# piezo-driver_v0_1-R002.net
KiCad netlist of a schematic drawn in EAGLE
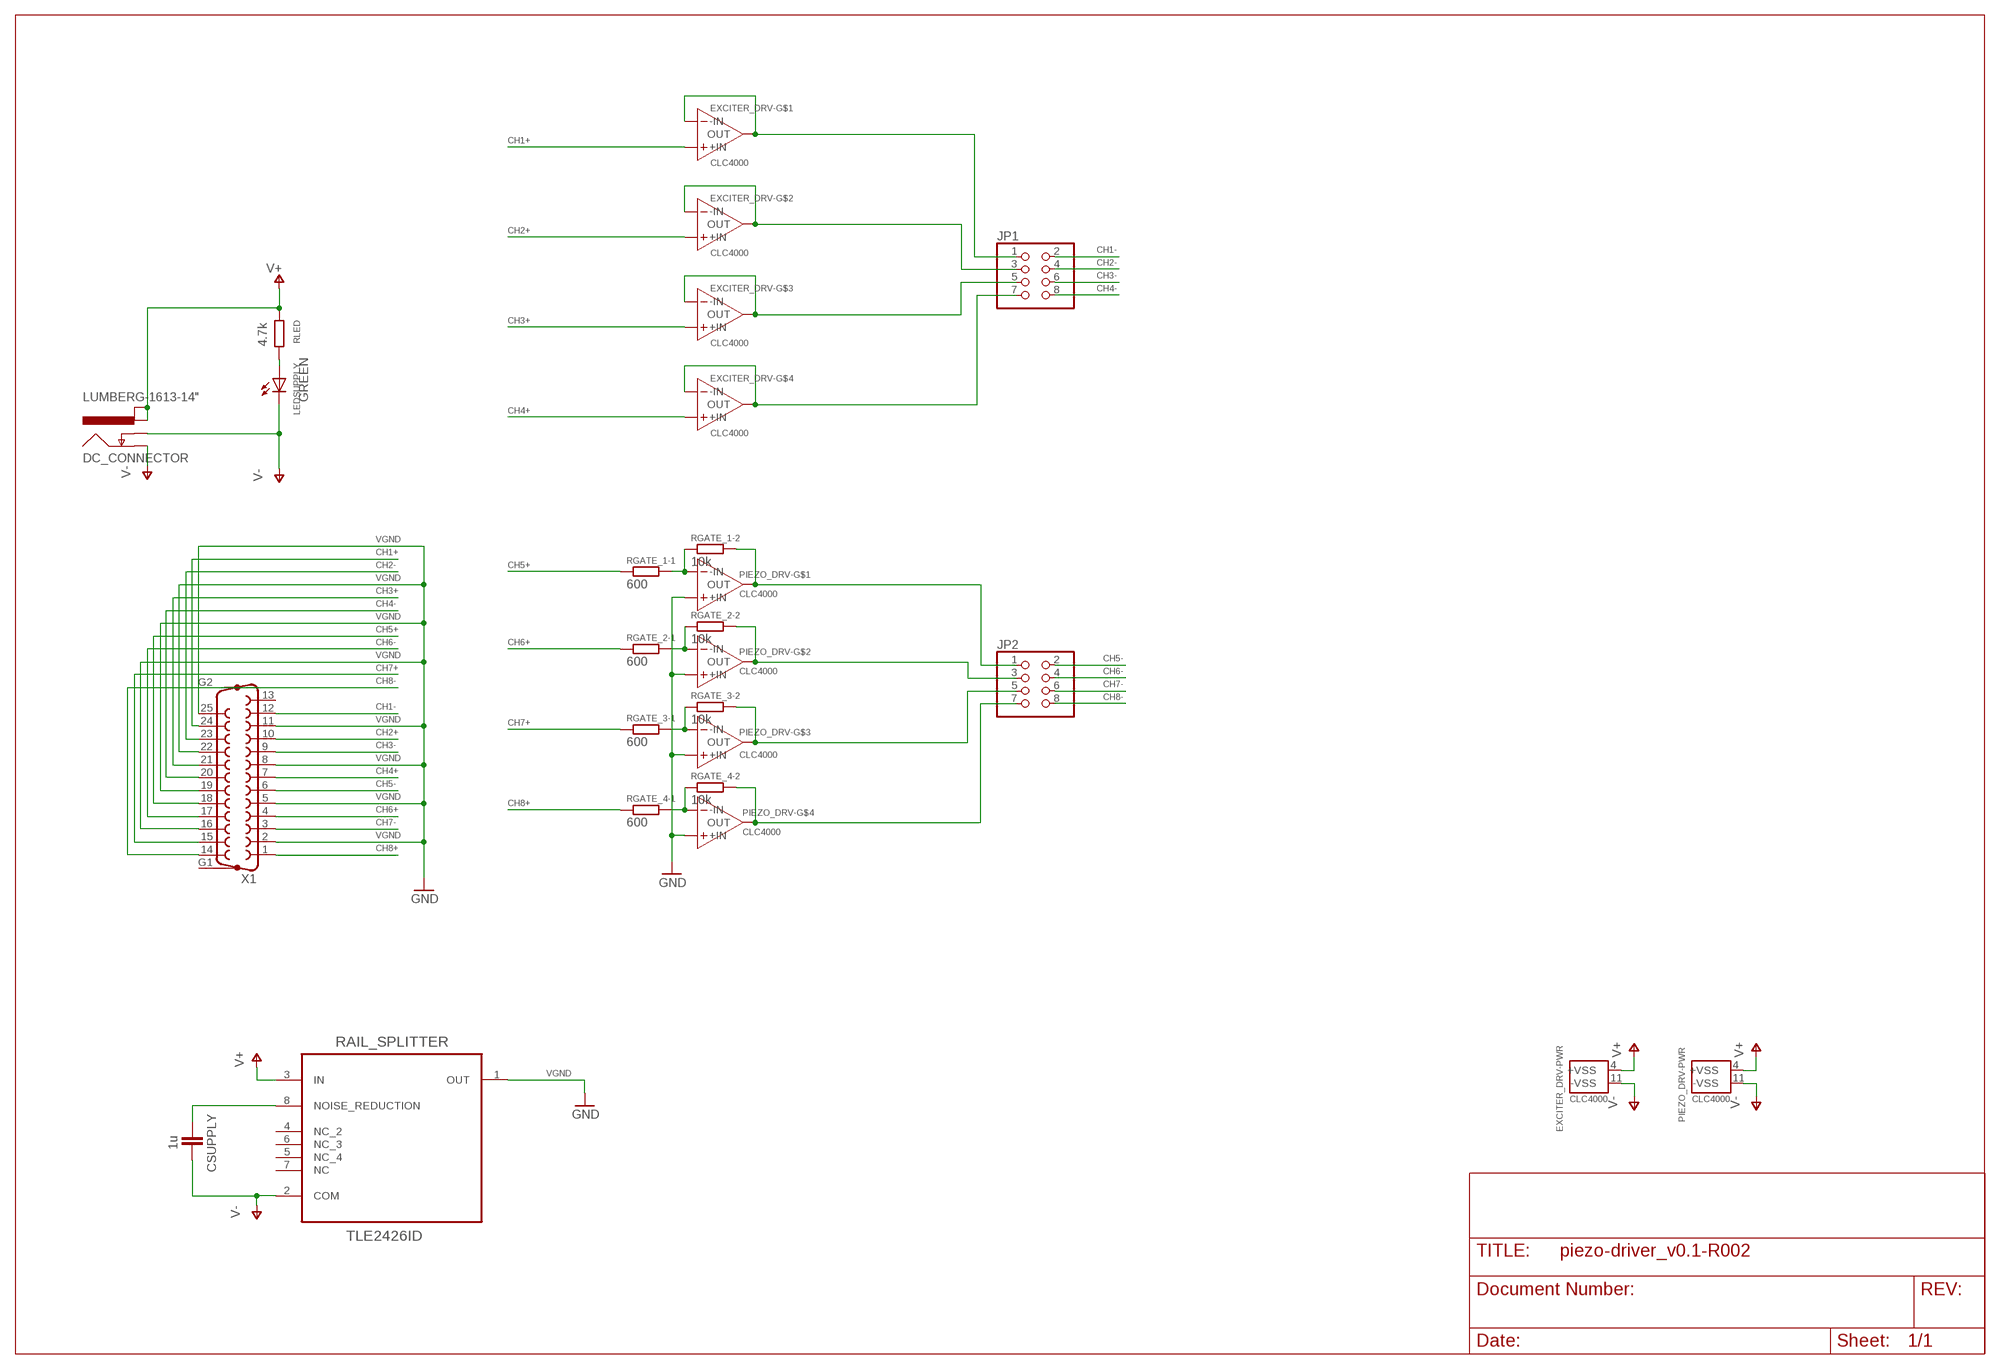
[diagram p0: schematic, sheet 1]

(export (version "E")
  (design (tool "Eeschema 10.0.6"))
  (components
    (comp (ref "CSUPPLY")
      (value "1u")
      (footprint "eagle-import:C0603")
      (libsource (lib "eagle-import") (part "C-EUC0603"))
    )
    (comp (ref "DC_CONNECTOR")
      (value "LUMBERG-1613-14\"")
      (footprint "eagle-import:LUMBERG-1613_14")
      (libsource (lib "eagle-import") (part "LUMBERG-1613-14{dblquote}"))
    )
    (comp (ref "EXCITER_DRV")
      (value "CLC4000")
      (footprint "eagle-import:SOIC-14")
      (libsource (lib "eagle-import") (part "CLC4000"))
    )
    (comp (ref "JP1")
      (value "PINHD-2X4/90")
      (footprint "eagle-import:2X04_90")
      (libsource (lib "eagle-import") (part "PINHD-2X4/90"))
    )
    (comp (ref "JP2")
      (value "PINHD-2X4/90")
      (footprint "eagle-import:2X04_90")
      (libsource (lib "eagle-import") (part "PINHD-2X4/90"))
    )
    (comp (ref "LEDSUPPLY")
      (value "GREEN")
      (footprint "eagle-import:LED3MM")
      (libsource (lib "eagle-import") (part "LED3MM"))
    )
    (comp (ref "PIEZO_DRV")
      (value "CLC4000")
      (footprint "eagle-import:SOIC-14")
      (libsource (lib "eagle-import") (part "CLC4000"))
    )
    (comp (ref "RAIL_SPLITTER")
      (value "TLE2426ID")
      (footprint "eagle-import:SOIC127P600X175-8N")
      (libsource (lib "eagle-import") (part "TLE2426ID"))
    )
    (comp (ref "RGATE_1-1")
      (value "600")
      (footprint "eagle-import:R0805")
      (libsource (lib "eagle-import") (part "R-EU_R0805"))
    )
    (comp (ref "RGATE_1-2")
      (value "10k")
      (footprint "eagle-import:R0805")
      (libsource (lib "eagle-import") (part "R-EU_R0805"))
    )
    (comp (ref "RGATE_2-1")
      (value "600")
      (footprint "eagle-import:R0805")
      (libsource (lib "eagle-import") (part "R-EU_R0805"))
    )
    (comp (ref "RGATE_2-2")
      (value "10k")
      (footprint "eagle-import:R0805")
      (libsource (lib "eagle-import") (part "R-EU_R0805"))
    )
    (comp (ref "RGATE_3-1")
      (value "600")
      (footprint "eagle-import:R0805")
      (libsource (lib "eagle-import") (part "R-EU_R0805"))
    )
    (comp (ref "RGATE_3-2")
      (value "10k")
      (footprint "eagle-import:R0805")
      (libsource (lib "eagle-import") (part "R-EU_R0805"))
    )
    (comp (ref "RGATE_4-1")
      (value "600")
      (footprint "eagle-import:R0805")
      (libsource (lib "eagle-import") (part "R-EU_R0805"))
    )
    (comp (ref "RGATE_4-2")
      (value "10k")
      (footprint "eagle-import:R0805")
      (libsource (lib "eagle-import") (part "R-EU_R0805"))
    )
    (comp (ref "RLED")
      (value "4.7k")
      (footprint "eagle-import:R0805")
      (libsource (lib "eagle-import") (part "R-EU_R0805"))
    )
    (comp (ref "X1")
      (value "F25HP")
      (footprint "eagle-import:F25HP")
      (libsource (lib "eagle-import") (part "F25HP"))
    )
  )
  (nets
    (net (code "1") (name "/CH1+") (class "Default")
      (node (ref "EXCITER_DRV") (pin "3") (pinfunction "+IN_3") (pintype "bidirectional"))
      (node (ref "X1") (pin "24") (pinfunction "24_24") (pintype "passive"))
    )
    (net (code "2") (name "/CH1-") (class "Default")
      (node (ref "JP1") (pin "2") (pinfunction "2_2") (pintype "passive"))
      (node (ref "X1") (pin "12") (pinfunction "12_12") (pintype "passive"))
    )
    (net (code "3") (name "/CH2+") (class "Default")
      (node (ref "EXCITER_DRV") (pin "5") (pinfunction "+IN_5") (pintype "bidirectional"))
      (node (ref "X1") (pin "10") (pinfunction "10_10") (pintype "passive"))
    )
    (net (code "4") (name "/CH2-") (class "Default")
      (node (ref "JP1") (pin "4") (pinfunction "4_4") (pintype "passive"))
      (node (ref "X1") (pin "23") (pinfunction "23_23") (pintype "passive"))
    )
    (net (code "5") (name "/CH3+") (class "Default")
      (node (ref "EXCITER_DRV") (pin "10") (pinfunction "+IN_10") (pintype "bidirectional"))
      (node (ref "X1") (pin "21") (pinfunction "21_21") (pintype "passive"))
    )
    (net (code "6") (name "/CH3-") (class "Default")
      (node (ref "JP1") (pin "6") (pinfunction "6_6") (pintype "passive"))
      (node (ref "X1") (pin "9") (pinfunction "9_9") (pintype "passive"))
    )
    (net (code "7") (name "/CH4+") (class "Default")
      (node (ref "EXCITER_DRV") (pin "12") (pinfunction "+IN_12") (pintype "bidirectional"))
      (node (ref "X1") (pin "7") (pinfunction "7_7") (pintype "passive"))
    )
    (net (code "8") (name "/CH4-") (class "Default")
      (node (ref "JP1") (pin "8") (pinfunction "8_8") (pintype "passive"))
      (node (ref "X1") (pin "20") (pinfunction "20_20") (pintype "passive"))
    )
    (net (code "9") (name "/CH5+") (class "Default")
      (node (ref "RGATE_1-1") (pin "1") (pinfunction "1_1") (pintype "passive"))
      (node (ref "X1") (pin "18") (pinfunction "18_18") (pintype "passive"))
    )
    (net (code "10") (name "/CH5-") (class "Default")
      (node (ref "JP2") (pin "2") (pinfunction "2_2") (pintype "passive"))
      (node (ref "X1") (pin "6") (pinfunction "6_6") (pintype "passive"))
    )
    (net (code "11") (name "/CH6+") (class "Default")
      (node (ref "RGATE_2-1") (pin "1") (pinfunction "1_1") (pintype "passive"))
      (node (ref "X1") (pin "4") (pinfunction "4_4") (pintype "passive"))
    )
    (net (code "12") (name "/CH6-") (class "Default")
      (node (ref "JP2") (pin "4") (pinfunction "4_4") (pintype "passive"))
      (node (ref "X1") (pin "17") (pinfunction "17_17") (pintype "passive"))
    )
    (net (code "13") (name "/CH7+") (class "Default")
      (node (ref "RGATE_3-1") (pin "1") (pinfunction "1_1") (pintype "passive"))
      (node (ref "X1") (pin "15") (pinfunction "15_15") (pintype "passive"))
    )
    (net (code "14") (name "/CH7-") (class "Default")
      (node (ref "JP2") (pin "6") (pinfunction "6_6") (pintype "passive"))
      (node (ref "X1") (pin "3") (pinfunction "3_3") (pintype "passive"))
    )
    (net (code "15") (name "/CH8+") (class "Default")
      (node (ref "RGATE_4-1") (pin "1") (pinfunction "1_1") (pintype "passive"))
      (node (ref "X1") (pin "1") (pinfunction "1_1") (pintype "passive"))
    )
    (net (code "16") (name "/CH8-") (class "Default")
      (node (ref "JP2") (pin "8") (pinfunction "8_8") (pintype "passive"))
      (node (ref "X1") (pin "14") (pinfunction "14_14") (pintype "passive"))
    )
    (net (code "17") (name "GND") (class "Default")
      (node (ref "PIEZO_DRV") (pin "10") (pinfunction "+IN_10") (pintype "bidirectional"))
      (node (ref "PIEZO_DRV") (pin "12") (pinfunction "+IN_12") (pintype "bidirectional"))
      (node (ref "PIEZO_DRV") (pin "3") (pinfunction "+IN_3") (pintype "bidirectional"))
      (node (ref "PIEZO_DRV") (pin "5") (pinfunction "+IN_5") (pintype "bidirectional"))
      (node (ref "RAIL_SPLITTER") (pin "1") (pinfunction "OUT_1") (pintype "output"))
      (node (ref "X1") (pin "11") (pinfunction "11_11") (pintype "passive"))
      (node (ref "X1") (pin "16") (pinfunction "16_16") (pintype "passive"))
      (node (ref "X1") (pin "19") (pinfunction "19_19") (pintype "passive"))
      (node (ref "X1") (pin "2") (pinfunction "2_2") (pintype "passive"))
      (node (ref "X1") (pin "22") (pinfunction "22_22") (pintype "passive"))
      (node (ref "X1") (pin "25") (pinfunction "25_25") (pintype "passive"))
      (node (ref "X1") (pin "5") (pinfunction "5_5") (pintype "passive"))
      (node (ref "X1") (pin "8") (pinfunction "8_8") (pintype "passive"))
    )
    (net (code "18") (name "Net-(EXCITER_DRVA--IN)") (class "Default")
      (node (ref "EXCITER_DRV") (pin "1") (pinfunction "OUT_1") (pintype "bidirectional"))
      (node (ref "EXCITER_DRV") (pin "2") (pinfunction "-IN_2") (pintype "bidirectional"))
      (node (ref "JP1") (pin "1") (pinfunction "1_1") (pintype "passive"))
    )
    (net (code "19") (name "Net-(EXCITER_DRVB--IN)") (class "Default")
      (node (ref "EXCITER_DRV") (pin "6") (pinfunction "-IN_6") (pintype "bidirectional"))
      (node (ref "EXCITER_DRV") (pin "7") (pinfunction "OUT_7") (pintype "bidirectional"))
      (node (ref "JP1") (pin "3") (pinfunction "3_3") (pintype "passive"))
    )
    (net (code "20") (name "Net-(EXCITER_DRVC--IN)") (class "Default")
      (node (ref "EXCITER_DRV") (pin "8") (pinfunction "OUT_8") (pintype "bidirectional"))
      (node (ref "EXCITER_DRV") (pin "9") (pinfunction "-IN_9") (pintype "bidirectional"))
      (node (ref "JP1") (pin "5") (pinfunction "5_5") (pintype "passive"))
    )
    (net (code "21") (name "Net-(EXCITER_DRVD--IN)") (class "Default")
      (node (ref "EXCITER_DRV") (pin "13") (pinfunction "-IN_13") (pintype "bidirectional"))
      (node (ref "EXCITER_DRV") (pin "14") (pinfunction "OUT_14") (pintype "bidirectional"))
      (node (ref "JP1") (pin "7") (pinfunction "7_7") (pintype "passive"))
    )
    (net (code "22") (name "Net-(LEDSUPPLY-PadA)") (class "Default")
      (node (ref "LEDSUPPLY") (pin "A") (pinfunction "A_A") (pintype "passive"))
      (node (ref "RLED") (pin "1") (pinfunction "1_1") (pintype "passive"))
    )
    (net (code "23") (name "Net-(PIEZO_DRVA--IN)") (class "Default")
      (node (ref "PIEZO_DRV") (pin "2") (pinfunction "-IN_2") (pintype "bidirectional"))
      (node (ref "RGATE_1-1") (pin "2") (pinfunction "2_2") (pintype "passive"))
      (node (ref "RGATE_1-2") (pin "1") (pinfunction "1_1") (pintype "passive"))
    )
    (net (code "24") (name "Net-(PIEZO_DRVA-OUT)") (class "Default")
      (node (ref "JP2") (pin "1") (pinfunction "1_1") (pintype "passive"))
      (node (ref "PIEZO_DRV") (pin "1") (pinfunction "OUT_1") (pintype "bidirectional"))
      (node (ref "RGATE_1-2") (pin "2") (pinfunction "2_2") (pintype "passive"))
    )
    (net (code "25") (name "Net-(PIEZO_DRVB--IN)") (class "Default")
      (node (ref "PIEZO_DRV") (pin "6") (pinfunction "-IN_6") (pintype "bidirectional"))
      (node (ref "RGATE_2-1") (pin "2") (pinfunction "2_2") (pintype "passive"))
      (node (ref "RGATE_2-2") (pin "1") (pinfunction "1_1") (pintype "passive"))
    )
    (net (code "26") (name "Net-(PIEZO_DRVB-OUT)") (class "Default")
      (node (ref "JP2") (pin "3") (pinfunction "3_3") (pintype "passive"))
      (node (ref "PIEZO_DRV") (pin "7") (pinfunction "OUT_7") (pintype "bidirectional"))
      (node (ref "RGATE_2-2") (pin "2") (pinfunction "2_2") (pintype "passive"))
    )
    (net (code "27") (name "Net-(PIEZO_DRVC--IN)") (class "Default")
      (node (ref "PIEZO_DRV") (pin "9") (pinfunction "-IN_9") (pintype "bidirectional"))
      (node (ref "RGATE_3-1") (pin "2") (pinfunction "2_2") (pintype "passive"))
      (node (ref "RGATE_3-2") (pin "1") (pinfunction "1_1") (pintype "passive"))
    )
    (net (code "28") (name "Net-(PIEZO_DRVC-OUT)") (class "Default")
      (node (ref "JP2") (pin "5") (pinfunction "5_5") (pintype "passive"))
      (node (ref "PIEZO_DRV") (pin "8") (pinfunction "OUT_8") (pintype "bidirectional"))
      (node (ref "RGATE_3-2") (pin "2") (pinfunction "2_2") (pintype "passive"))
    )
    (net (code "29") (name "Net-(PIEZO_DRVD--IN)") (class "Default")
      (node (ref "PIEZO_DRV") (pin "13") (pinfunction "-IN_13") (pintype "bidirectional"))
      (node (ref "RGATE_4-1") (pin "2") (pinfunction "2_2") (pintype "passive"))
      (node (ref "RGATE_4-2") (pin "1") (pinfunction "1_1") (pintype "passive"))
    )
    (net (code "30") (name "Net-(PIEZO_DRVD-OUT)") (class "Default")
      (node (ref "JP2") (pin "7") (pinfunction "7_7") (pintype "passive"))
      (node (ref "PIEZO_DRV") (pin "14") (pinfunction "OUT_14") (pintype "bidirectional"))
      (node (ref "RGATE_4-2") (pin "2") (pinfunction "2_2") (pintype "passive"))
    )
    (net (code "31") (name "Net-(RAIL_SPLITTER-NOISE_REDUCTION)") (class "Default")
      (node (ref "CSUPPLY") (pin "1") (pinfunction "1_1") (pintype "passive"))
      (node (ref "RAIL_SPLITTER") (pin "8") (pinfunction "NOISE_REDUCTION_8") (pintype "passive"))
    )
    (net (code "32") (name "V+") (class "Default")
      (node (ref "DC_CONNECTOR") (pin "3") (pinfunction "PWR_1_3") (pintype "power_in"))
      (node (ref "DC_CONNECTOR") (pin "4") (pinfunction "PWR_2_4") (pintype "power_in"))
      (node (ref "EXCITER_DRV") (pin "4") (pinfunction "+VSS_4") (pintype "power_in"))
      (node (ref "PIEZO_DRV") (pin "4") (pinfunction "+VSS_4") (pintype "power_in"))
      (node (ref "RAIL_SPLITTER") (pin "3") (pinfunction "IN_3") (pintype "input"))
      (node (ref "RLED") (pin "2") (pinfunction "2_2") (pintype "passive"))
    )
    (net (code "33") (name "V-") (class "Default")
      (node (ref "CSUPPLY") (pin "2") (pinfunction "2_2") (pintype "passive"))
      (node (ref "DC_CONNECTOR") (pin "1") (pinfunction "GND_1") (pintype "power_in"))
      (node (ref "DC_CONNECTOR") (pin "2") (pinfunction "GND_INS_2") (pintype "power_in"))
      (node (ref "EXCITER_DRV") (pin "11") (pinfunction "-VSS_11") (pintype "power_in"))
      (node (ref "LEDSUPPLY") (pin "K") (pinfunction "C_K") (pintype "passive"))
      (node (ref "PIEZO_DRV") (pin "11") (pinfunction "-VSS_11") (pintype "power_in"))
      (node (ref "RAIL_SPLITTER") (pin "2") (pinfunction "COM_2") (pintype "passive"))
    )
    (net (code "34") (name "unconnected-(RAIL_SPLITTER-NC-Pad7)") (class "Default")
      (node (ref "RAIL_SPLITTER") (pin "7") (pinfunction "NC_7") (pintype "no_connect"))
    )
    (net (code "35") (name "unconnected-(RAIL_SPLITTER-NC_2-Pad4)") (class "Default")
      (node (ref "RAIL_SPLITTER") (pin "4") (pinfunction "NC_2_4") (pintype "no_connect"))
    )
    (net (code "36") (name "unconnected-(RAIL_SPLITTER-NC_3-Pad6)") (class "Default")
      (node (ref "RAIL_SPLITTER") (pin "6") (pinfunction "NC_3_6") (pintype "no_connect"))
    )
    (net (code "37") (name "unconnected-(RAIL_SPLITTER-NC_4-Pad5)") (class "Default")
      (node (ref "RAIL_SPLITTER") (pin "5") (pinfunction "NC_4_5") (pintype "no_connect"))
    )
    (net (code "38") (name "unconnected-(X1-Pad13)") (class "Default")
      (node (ref "X1") (pin "13") (pinfunction "13_13") (pintype "passive"))
    )
    (net (code "39") (name "unconnected-(X1-PadG1)") (class "Default")
      (node (ref "X1") (pin "G1") (pinfunction "G1_G1") (pintype "passive"))
    )
    (net (code "40") (name "unconnected-(X1-PadG2)") (class "Default")
      (node (ref "X1") (pin "G2") (pinfunction "G2_G2") (pintype "passive"))
    )
  )
)
